# battery_holder.net
KiCad netlist of a schematic drawn in EAGLE
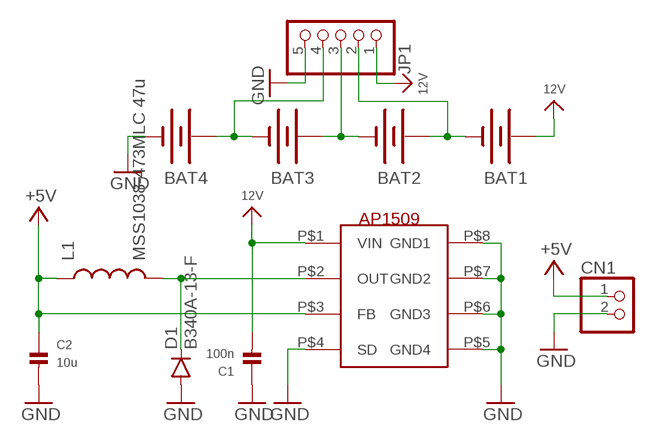
[diagram p0: schematic, sheet 1]

(export (version "E")
  (design (tool "Eeschema 10.0.6"))
  (components
    (comp (ref "BAT1")
      (value "BATTERY18650")
      (footprint "eagle-import:BATTERY_18650-HOLDER")
      (libsource (lib "eagle-import") (part "BATTERY18650"))
    )
    (comp (ref "BAT2")
      (value "BATTERY18650")
      (footprint "eagle-import:BATTERY_18650-HOLDER")
      (libsource (lib "eagle-import") (part "BATTERY18650"))
    )
    (comp (ref "BAT3")
      (value "BATTERY18650")
      (footprint "eagle-import:BATTERY_18650-HOLDER")
      (libsource (lib "eagle-import") (part "BATTERY18650"))
    )
    (comp (ref "BAT4")
      (value "BATTERY18650")
      (footprint "eagle-import:BATTERY_18650-HOLDER")
      (libsource (lib "eagle-import") (part "BATTERY18650"))
    )
    (comp (ref "C1")
      (value "100n")
      (footprint "eagle-import:_0603MP")
      (libsource (lib "eagle-import") (part "CAP_CERAMIC_0603MP"))
    )
    (comp (ref "C2")
      (value "10u")
      (footprint "eagle-import:_0805MP")
      (libsource (lib "eagle-import") (part "CAP_CERAMIC_0805MP"))
    )
    (comp (ref "CN1")
      (value "JST_2PIN")
      (footprint "eagle-import:JSTPH2")
      (libsource (lib "eagle-import") (part "JST_2PIN"))
    )
    (comp (ref "D1")
      (value "B340A-13-F")
      (footprint "eagle-import:SMA-DIODE")
      (libsource (lib "eagle-import") (part "DIODESMA"))
    )
    (comp (ref "JP1")
      (value "PINHD-1X5/90")
      (footprint "eagle-import:1X05_90")
      (libsource (lib "eagle-import") (part "PINHD-1X5/90"))
    )
    (comp (ref "L1")
      (value "MSS1038-473MLC 47u")
      (footprint "eagle-import:CDRH125")
      (libsource (lib "eagle-import") (part "INDUCTORPWR"))
    )
    (comp (ref "U$3")
      (value "AP1509")
      (footprint "eagle-import:SOP-8L")
      (libsource (lib "eagle-import") (part "AP1509"))
    )
  )
  (nets
    (net (code "1") (name "+5V") (class "Default")
      (node (ref "C2") (pin "1") (pinfunction "P$1_1") (pintype "passive"))
      (node (ref "CN1") (pin "1") (pinfunction "1_1") (pintype "passive"))
      (node (ref "L1") (pin "1") (pinfunction "1_1") (pintype "passive"))
      (node (ref "U$3") (pin "P$3") (pinfunction "FB_P$3") (pintype "bidirectional"))
    )
    (net (code "2") (name "12V") (class "Default")
      (node (ref "BAT1") (pin "PWR@1") (pinfunction "+_PWR@1") (pintype "power_in"))
      (node (ref "C1") (pin "2") (pinfunction "P$2_2") (pintype "passive"))
      (node (ref "JP1") (pin "1") (pinfunction "1_1") (pintype "passive"))
      (node (ref "U$3") (pin "P$1") (pinfunction "VIN_P$1") (pintype "bidirectional"))
    )
    (net (code "3") (name "GND") (class "Default")
      (node (ref "BAT4") (pin "GND@1") (pinfunction "-_GND@1") (pintype "power_in"))
      (node (ref "C1") (pin "1") (pinfunction "P$1_1") (pintype "passive"))
      (node (ref "C2") (pin "2") (pinfunction "P$2_2") (pintype "passive"))
      (node (ref "CN1") (pin "2") (pinfunction "2_2") (pintype "passive"))
      (node (ref "D1") (pin "A") (pinfunction "A_A") (pintype "passive"))
      (node (ref "JP1") (pin "5") (pinfunction "5_5") (pintype "passive"))
      (node (ref "U$3") (pin "P$4") (pinfunction "SD_P$4") (pintype "bidirectional"))
      (node (ref "U$3") (pin "P$5") (pinfunction "GND4_P$5") (pintype "bidirectional"))
      (node (ref "U$3") (pin "P$6") (pinfunction "GND3_P$6") (pintype "bidirectional"))
      (node (ref "U$3") (pin "P$7") (pinfunction "GND2_P$7") (pintype "bidirectional"))
      (node (ref "U$3") (pin "P$8") (pinfunction "GND1_P$8") (pintype "bidirectional"))
    )
    (net (code "4") (name "Net-(BAT1--)") (class "Default")
      (node (ref "BAT1") (pin "GND@1") (pinfunction "-_GND@1") (pintype "power_in"))
      (node (ref "BAT2") (pin "PWR@1") (pinfunction "+_PWR@1") (pintype "power_in"))
      (node (ref "JP1") (pin "2") (pinfunction "2_2") (pintype "passive"))
    )
    (net (code "5") (name "Net-(BAT2--)") (class "Default")
      (node (ref "BAT2") (pin "GND@1") (pinfunction "-_GND@1") (pintype "power_in"))
      (node (ref "BAT3") (pin "PWR@1") (pinfunction "+_PWR@1") (pintype "power_in"))
      (node (ref "JP1") (pin "3") (pinfunction "3_3") (pintype "passive"))
    )
    (net (code "6") (name "Net-(BAT3--)") (class "Default")
      (node (ref "BAT3") (pin "GND@1") (pinfunction "-_GND@1") (pintype "power_in"))
      (node (ref "BAT4") (pin "PWR@1") (pinfunction "+_PWR@1") (pintype "power_in"))
      (node (ref "JP1") (pin "4") (pinfunction "4_4") (pintype "passive"))
    )
    (net (code "7") (name "Net-(U$3-OUT)") (class "Default")
      (node (ref "D1") (pin "C") (pinfunction "C_C") (pintype "passive"))
      (node (ref "L1") (pin "2") (pinfunction "2_2") (pintype "passive"))
      (node (ref "U$3") (pin "P$2") (pinfunction "OUT_P$2") (pintype "bidirectional"))
    )
  )
)
